# Temp_Sensor.net
KiCad netlist of a schematic drawn in Altium Designer
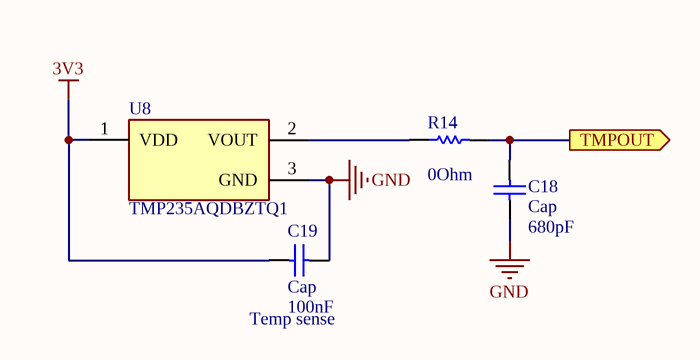
[diagram p0: Temp Sensor.SchDoc]

(export (version "E")
  (design (tool "Eeschema 10.0.6"))
  (components
    (comp (ref "C18")
      (value "Cap")
      (footprint "1608[0603]")
      (description "Capacitor")
      (fields (field (name "ALTIUM_VALUE") "680pF") (field (name "PUBLISHER") "Altium Limited"))
      (libsource (lib "Miscellaneous Devices") (part "Cap"))
    )
    (comp (ref "C19")
      (value "Cap")
      (footprint "1608[0603]")
      (description "Capacitor")
      (fields (field (name "ALTIUM_VALUE") "100nF") (field (name "PUBLISHER") "Altium Limited"))
      (libsource (lib "Miscellaneous Devices") (part "Cap"))
    )
    (comp (ref "R14")
      (value "0Ohm")
      (footprint "0402-A")
      (description "Resistor")
      (fields (field (name "Comment") "Res1") (field (name "PUBLISHER") "Altium Limited"))
      (libsource (lib "Miscellaneous Devices") (part "Res1"))
    )
    (comp (ref "U8")
      (value "TMP235AQDBZTQ1")
      (footprint "FP-DBZ0003A-MFG")
      (description "LOW-POWER HIGH-ACCURACY ANALOG O")
      (fields
        (field (name "MANUFACTURER") "Texas Instruments")
        (field (name "MANUFACTURER PART NUMBER") "TMP235A2DBZR")
      )
      (libsource (lib "Altium Content Vault") (part "1212246baba8f64ab0dd7b63bd818eb"))
    )
  )
  (nets
    (net (code "1") (name "/TMPOUT") (class "Default")
      (node (ref "C18") (pin "2") (pinfunction "2_2") (pintype "passive"))
      (node (ref "R14") (pin "2") (pinfunction "2_2") (pintype "passive"))
    )
    (net (code "2") (name "3V3") (class "Default")
      (node (ref "C19") (pin "2") (pinfunction "2_2") (pintype "passive"))
      (node (ref "U8") (pin "1") (pinfunction "VDD_1") (pintype "power_in"))
    )
    (net (code "3") (name "GND") (class "Default")
      (node (ref "C18") (pin "1") (pinfunction "1_1") (pintype "passive"))
      (node (ref "C19") (pin "1") (pinfunction "1_1") (pintype "passive"))
      (node (ref "U8") (pin "3") (pinfunction "GND_3") (pintype "power_in"))
    )
    (net (code "4") (name "Net-(U8-VOUT)") (class "Default")
      (node (ref "R14") (pin "1") (pinfunction "1_1") (pintype "passive"))
      (node (ref "U8") (pin "2") (pinfunction "VOUT_2") (pintype "passive"))
    )
  )
)
